# RPI_SSD1963.net
KiCad netlist of a schematic drawn in EAGLE
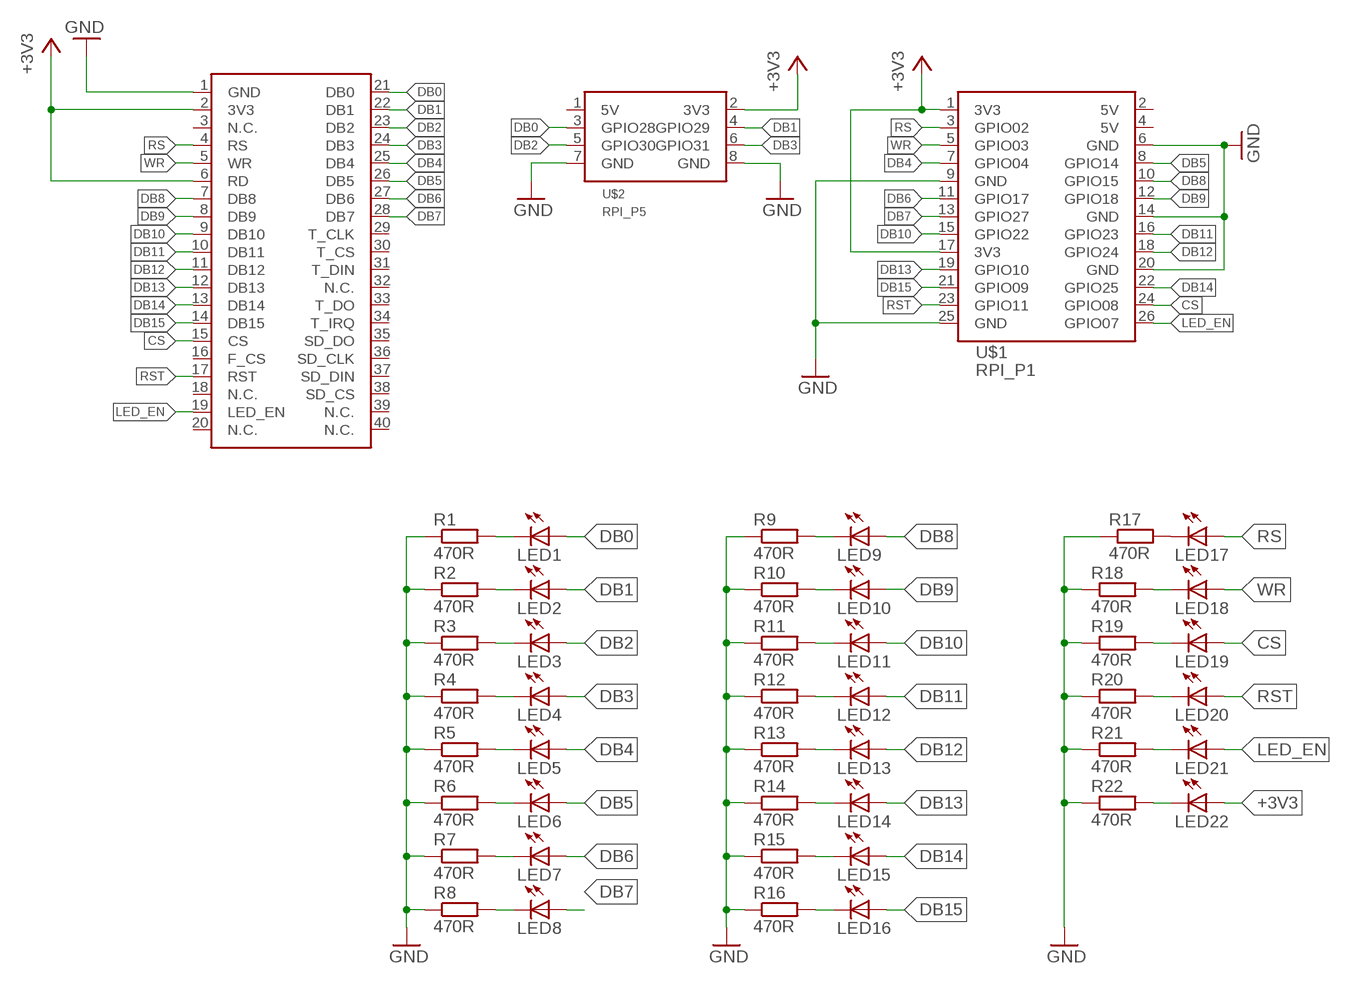
[diagram p0: schematic, sheet 1]

(export (version "E")
  (design (tool "Eeschema 10.0.6"))
  (components
    (comp (ref "LED1")
      (value "LEDCHIP-LED0603")
      (footprint "eagle-import:CHIP-LED0603")
      (libsource (lib "eagle-import") (part "LEDCHIP-LED0603"))
    )
    (comp (ref "LED2")
      (value "LEDCHIP-LED0603")
      (footprint "eagle-import:CHIP-LED0603")
      (libsource (lib "eagle-import") (part "LEDCHIP-LED0603"))
    )
    (comp (ref "LED3")
      (value "LEDCHIP-LED0603")
      (footprint "eagle-import:CHIP-LED0603")
      (libsource (lib "eagle-import") (part "LEDCHIP-LED0603"))
    )
    (comp (ref "LED4")
      (value "LEDCHIP-LED0603")
      (footprint "eagle-import:CHIP-LED0603")
      (libsource (lib "eagle-import") (part "LEDCHIP-LED0603"))
    )
    (comp (ref "LED5")
      (value "LEDCHIP-LED0603")
      (footprint "eagle-import:CHIP-LED0603")
      (libsource (lib "eagle-import") (part "LEDCHIP-LED0603"))
    )
    (comp (ref "LED6")
      (value "LEDCHIP-LED0603")
      (footprint "eagle-import:CHIP-LED0603")
      (libsource (lib "eagle-import") (part "LEDCHIP-LED0603"))
    )
    (comp (ref "LED7")
      (value "LEDCHIP-LED0603")
      (footprint "eagle-import:CHIP-LED0603")
      (libsource (lib "eagle-import") (part "LEDCHIP-LED0603"))
    )
    (comp (ref "LED8")
      (value "LEDCHIP-LED0603")
      (footprint "eagle-import:CHIP-LED0603")
      (libsource (lib "eagle-import") (part "LEDCHIP-LED0603"))
    )
    (comp (ref "LED9")
      (value "LEDCHIP-LED0603")
      (footprint "eagle-import:CHIP-LED0603")
      (libsource (lib "eagle-import") (part "LEDCHIP-LED0603"))
    )
    (comp (ref "LED10")
      (value "LEDCHIP-LED0603")
      (footprint "eagle-import:CHIP-LED0603")
      (libsource (lib "eagle-import") (part "LEDCHIP-LED0603"))
    )
    (comp (ref "LED11")
      (value "LEDCHIP-LED0603")
      (footprint "eagle-import:CHIP-LED0603")
      (libsource (lib "eagle-import") (part "LEDCHIP-LED0603"))
    )
    (comp (ref "LED12")
      (value "LEDCHIP-LED0603")
      (footprint "eagle-import:CHIP-LED0603")
      (libsource (lib "eagle-import") (part "LEDCHIP-LED0603"))
    )
    (comp (ref "LED13")
      (value "LEDCHIP-LED0603")
      (footprint "eagle-import:CHIP-LED0603")
      (libsource (lib "eagle-import") (part "LEDCHIP-LED0603"))
    )
    (comp (ref "LED14")
      (value "LEDCHIP-LED0603")
      (footprint "eagle-import:CHIP-LED0603")
      (libsource (lib "eagle-import") (part "LEDCHIP-LED0603"))
    )
    (comp (ref "LED15")
      (value "LEDCHIP-LED0603")
      (footprint "eagle-import:CHIP-LED0603")
      (libsource (lib "eagle-import") (part "LEDCHIP-LED0603"))
    )
    (comp (ref "LED16")
      (value "LEDCHIP-LED0603")
      (footprint "eagle-import:CHIP-LED0603")
      (libsource (lib "eagle-import") (part "LEDCHIP-LED0603"))
    )
    (comp (ref "LED17")
      (value "LEDCHIP-LED0603")
      (footprint "eagle-import:CHIP-LED0603")
      (libsource (lib "eagle-import") (part "LEDCHIP-LED0603"))
    )
    (comp (ref "LED18")
      (value "LEDCHIP-LED0603")
      (footprint "eagle-import:CHIP-LED0603")
      (libsource (lib "eagle-import") (part "LEDCHIP-LED0603"))
    )
    (comp (ref "LED19")
      (value "LEDCHIP-LED0603")
      (footprint "eagle-import:CHIP-LED0603")
      (libsource (lib "eagle-import") (part "LEDCHIP-LED0603"))
    )
    (comp (ref "LED20")
      (value "LEDCHIP-LED0603")
      (footprint "eagle-import:CHIP-LED0603")
      (libsource (lib "eagle-import") (part "LEDCHIP-LED0603"))
    )
    (comp (ref "LED21")
      (value "LEDCHIP-LED0603")
      (footprint "eagle-import:CHIP-LED0603")
      (libsource (lib "eagle-import") (part "LEDCHIP-LED0603"))
    )
    (comp (ref "LED22")
      (value "LEDCHIP-LED0603")
      (footprint "eagle-import:CHIP-LED0603")
      (libsource (lib "eagle-import") (part "LEDCHIP-LED0603"))
    )
    (comp (ref "R1")
      (value "470R")
      (footprint "eagle-import:R0402")
      (libsource (lib "eagle-import") (part "R-EU_R0402"))
    )
    (comp (ref "R2")
      (value "470R")
      (footprint "eagle-import:R0402")
      (libsource (lib "eagle-import") (part "R-EU_R0402"))
    )
    (comp (ref "R3")
      (value "470R")
      (footprint "eagle-import:R0402")
      (libsource (lib "eagle-import") (part "R-EU_R0402"))
    )
    (comp (ref "R4")
      (value "470R")
      (footprint "eagle-import:R0402")
      (libsource (lib "eagle-import") (part "R-EU_R0402"))
    )
    (comp (ref "R5")
      (value "470R")
      (footprint "eagle-import:R0402")
      (libsource (lib "eagle-import") (part "R-EU_R0402"))
    )
    (comp (ref "R6")
      (value "470R")
      (footprint "eagle-import:R0402")
      (libsource (lib "eagle-import") (part "R-EU_R0402"))
    )
    (comp (ref "R7")
      (value "470R")
      (footprint "eagle-import:R0402")
      (libsource (lib "eagle-import") (part "R-EU_R0402"))
    )
    (comp (ref "R8")
      (value "470R")
      (footprint "eagle-import:R0402")
      (libsource (lib "eagle-import") (part "R-EU_R0402"))
    )
    (comp (ref "R9")
      (value "470R")
      (footprint "eagle-import:R0402")
      (libsource (lib "eagle-import") (part "R-EU_R0402"))
    )
    (comp (ref "R10")
      (value "470R")
      (footprint "eagle-import:R0402")
      (libsource (lib "eagle-import") (part "R-EU_R0402"))
    )
    (comp (ref "R11")
      (value "470R")
      (footprint "eagle-import:R0402")
      (libsource (lib "eagle-import") (part "R-EU_R0402"))
    )
    (comp (ref "R12")
      (value "470R")
      (footprint "eagle-import:R0402")
      (libsource (lib "eagle-import") (part "R-EU_R0402"))
    )
    (comp (ref "R13")
      (value "470R")
      (footprint "eagle-import:R0402")
      (libsource (lib "eagle-import") (part "R-EU_R0402"))
    )
    (comp (ref "R14")
      (value "470R")
      (footprint "eagle-import:R0402")
      (libsource (lib "eagle-import") (part "R-EU_R0402"))
    )
    (comp (ref "R15")
      (value "470R")
      (footprint "eagle-import:R0402")
      (libsource (lib "eagle-import") (part "R-EU_R0402"))
    )
    (comp (ref "R16")
      (value "470R")
      (footprint "eagle-import:R0402")
      (libsource (lib "eagle-import") (part "R-EU_R0402"))
    )
    (comp (ref "R17")
      (value "470R")
      (footprint "eagle-import:R0402")
      (libsource (lib "eagle-import") (part "R-EU_R0402"))
    )
    (comp (ref "R18")
      (value "470R")
      (footprint "eagle-import:R0402")
      (libsource (lib "eagle-import") (part "R-EU_R0402"))
    )
    (comp (ref "R19")
      (value "470R")
      (footprint "eagle-import:R0402")
      (libsource (lib "eagle-import") (part "R-EU_R0402"))
    )
    (comp (ref "R20")
      (value "470R")
      (footprint "eagle-import:R0402")
      (libsource (lib "eagle-import") (part "R-EU_R0402"))
    )
    (comp (ref "R21")
      (value "470R")
      (footprint "eagle-import:R0402")
      (libsource (lib "eagle-import") (part "R-EU_R0402"))
    )
    (comp (ref "R22")
      (value "470R")
      (footprint "eagle-import:R0402")
      (libsource (lib "eagle-import") (part "R-EU_R0402"))
    )
    (comp (ref "U$1")
      (value "RPI_P1")
      (footprint "eagle-import:RPI_P1")
      (libsource (lib "eagle-import") (part "RPI_P1"))
    )
    (comp (ref "U$2")
      (value "RPI_P5")
      (footprint "eagle-import:RPI_P5")
      (libsource (lib "eagle-import") (part "RPI_P5"))
    )
    (comp (ref "U$3")
      (value "SSD1963")
      (footprint "eagle-import:SSD1963")
      (libsource (lib "eagle-import") (part "SSD1963"))
    )
  )
  (nets
    (net (code "1") (name "+3V3") (class "Default")
      (node (ref "LED22") (pin "A") (pinfunction "A_A") (pintype "passive"))
      (node (ref "U$1") (pin "1") (pinfunction "3V3_1") (pintype "bidirectional"))
      (node (ref "U$1") (pin "17") (pinfunction "3V3_17") (pintype "bidirectional"))
      (node (ref "U$2") (pin "2") (pinfunction "3V3_2") (pintype "bidirectional"))
      (node (ref "U$3") (pin "2") (pinfunction "3V3_2") (pintype "passive"))
      (node (ref "U$3") (pin "6") (pinfunction "RD_6") (pintype "bidirectional"))
    )
    (net (code "2") (name "CS") (class "Default")
      (node (ref "LED19") (pin "A") (pinfunction "A_A") (pintype "passive"))
      (node (ref "U$1") (pin "24") (pinfunction "GPIO08_24") (pintype "bidirectional"))
      (node (ref "U$3") (pin "15") (pinfunction "CS_15") (pintype "bidirectional"))
    )
    (net (code "3") (name "DB0") (class "Default")
      (node (ref "LED1") (pin "A") (pinfunction "A_A") (pintype "passive"))
      (node (ref "U$2") (pin "3") (pinfunction "GPIO28_3") (pintype "bidirectional"))
      (node (ref "U$3") (pin "21") (pinfunction "DB0_21") (pintype "bidirectional"))
    )
    (net (code "4") (name "DB1") (class "Default")
      (node (ref "LED2") (pin "A") (pinfunction "A_A") (pintype "passive"))
      (node (ref "U$2") (pin "4") (pinfunction "GPIO29_4") (pintype "bidirectional"))
      (node (ref "U$3") (pin "22") (pinfunction "DB1_22") (pintype "bidirectional"))
    )
    (net (code "5") (name "DB2") (class "Default")
      (node (ref "LED3") (pin "A") (pinfunction "A_A") (pintype "passive"))
      (node (ref "U$2") (pin "5") (pinfunction "GPIO30_5") (pintype "bidirectional"))
      (node (ref "U$3") (pin "23") (pinfunction "DB2_23") (pintype "bidirectional"))
    )
    (net (code "6") (name "DB3") (class "Default")
      (node (ref "LED4") (pin "A") (pinfunction "A_A") (pintype "passive"))
      (node (ref "U$2") (pin "6") (pinfunction "GPIO31_6") (pintype "bidirectional"))
      (node (ref "U$3") (pin "24") (pinfunction "DB3_24") (pintype "bidirectional"))
    )
    (net (code "7") (name "DB4") (class "Default")
      (node (ref "LED5") (pin "A") (pinfunction "A_A") (pintype "passive"))
      (node (ref "U$1") (pin "7") (pinfunction "GPIO04_7") (pintype "bidirectional"))
      (node (ref "U$3") (pin "25") (pinfunction "DB4_25") (pintype "bidirectional"))
    )
    (net (code "8") (name "DB5") (class "Default")
      (node (ref "LED6") (pin "A") (pinfunction "A_A") (pintype "passive"))
      (node (ref "U$1") (pin "8") (pinfunction "GPIO14_8") (pintype "bidirectional"))
      (node (ref "U$3") (pin "26") (pinfunction "DB5_26") (pintype "bidirectional"))
    )
    (net (code "9") (name "DB6") (class "Default")
      (node (ref "LED7") (pin "A") (pinfunction "A_A") (pintype "passive"))
      (node (ref "U$1") (pin "11") (pinfunction "GPIO17_11") (pintype "bidirectional"))
      (node (ref "U$3") (pin "27") (pinfunction "DB6_27") (pintype "bidirectional"))
    )
    (net (code "10") (name "DB7") (class "Default")
      (node (ref "LED8") (pin "A") (pinfunction "A_A") (pintype "passive"))
      (node (ref "U$1") (pin "13") (pinfunction "GPIO27_13") (pintype "bidirectional"))
      (node (ref "U$3") (pin "28") (pinfunction "DB7_28") (pintype "bidirectional"))
    )
    (net (code "11") (name "DB8") (class "Default")
      (node (ref "LED9") (pin "A") (pinfunction "A_A") (pintype "passive"))
      (node (ref "U$1") (pin "10") (pinfunction "GPIO15_10") (pintype "bidirectional"))
      (node (ref "U$3") (pin "7") (pinfunction "DB8_7") (pintype "bidirectional"))
    )
    (net (code "12") (name "DB9") (class "Default")
      (node (ref "LED10") (pin "A") (pinfunction "A_A") (pintype "passive"))
      (node (ref "U$1") (pin "12") (pinfunction "GPIO18_12") (pintype "bidirectional"))
      (node (ref "U$3") (pin "8") (pinfunction "DB9_8") (pintype "bidirectional"))
    )
    (net (code "13") (name "DB10") (class "Default")
      (node (ref "LED11") (pin "A") (pinfunction "A_A") (pintype "passive"))
      (node (ref "U$1") (pin "15") (pinfunction "GPIO22_15") (pintype "bidirectional"))
      (node (ref "U$3") (pin "9") (pinfunction "DB10_9") (pintype "bidirectional"))
    )
    (net (code "14") (name "DB11") (class "Default")
      (node (ref "LED12") (pin "A") (pinfunction "A_A") (pintype "passive"))
      (node (ref "U$1") (pin "16") (pinfunction "GPIO23_16") (pintype "bidirectional"))
      (node (ref "U$3") (pin "10") (pinfunction "DB11_10") (pintype "bidirectional"))
    )
    (net (code "15") (name "DB12") (class "Default")
      (node (ref "LED13") (pin "A") (pinfunction "A_A") (pintype "passive"))
      (node (ref "U$1") (pin "18") (pinfunction "GPIO24_18") (pintype "bidirectional"))
      (node (ref "U$3") (pin "11") (pinfunction "DB12_11") (pintype "bidirectional"))
    )
    (net (code "16") (name "DB13") (class "Default")
      (node (ref "LED14") (pin "A") (pinfunction "A_A") (pintype "passive"))
      (node (ref "U$1") (pin "19") (pinfunction "GPIO10_19") (pintype "bidirectional"))
      (node (ref "U$3") (pin "12") (pinfunction "DB13_12") (pintype "bidirectional"))
    )
    (net (code "17") (name "DB14") (class "Default")
      (node (ref "LED15") (pin "A") (pinfunction "A_A") (pintype "passive"))
      (node (ref "U$1") (pin "22") (pinfunction "GPIO25_22") (pintype "bidirectional"))
      (node (ref "U$3") (pin "13") (pinfunction "DB14_13") (pintype "bidirectional"))
    )
    (net (code "18") (name "DB15") (class "Default")
      (node (ref "LED16") (pin "A") (pinfunction "A_A") (pintype "passive"))
      (node (ref "U$1") (pin "21") (pinfunction "GPIO09_21") (pintype "bidirectional"))
      (node (ref "U$3") (pin "14") (pinfunction "DB15_14") (pintype "bidirectional"))
    )
    (net (code "19") (name "GND") (class "Default")
      (node (ref "R1") (pin "1") (pinfunction "1_1") (pintype "passive"))
      (node (ref "R10") (pin "1") (pinfunction "1_1") (pintype "passive"))
      (node (ref "R11") (pin "1") (pinfunction "1_1") (pintype "passive"))
      (node (ref "R12") (pin "1") (pinfunction "1_1") (pintype "passive"))
      (node (ref "R13") (pin "1") (pinfunction "1_1") (pintype "passive"))
      (node (ref "R14") (pin "1") (pinfunction "1_1") (pintype "passive"))
      (node (ref "R15") (pin "1") (pinfunction "1_1") (pintype "passive"))
      (node (ref "R16") (pin "1") (pinfunction "1_1") (pintype "passive"))
      (node (ref "R17") (pin "1") (pinfunction "1_1") (pintype "passive"))
      (node (ref "R18") (pin "1") (pinfunction "1_1") (pintype "passive"))
      (node (ref "R19") (pin "1") (pinfunction "1_1") (pintype "passive"))
      (node (ref "R2") (pin "1") (pinfunction "1_1") (pintype "passive"))
      (node (ref "R20") (pin "1") (pinfunction "1_1") (pintype "passive"))
      (node (ref "R21") (pin "1") (pinfunction "1_1") (pintype "passive"))
      (node (ref "R22") (pin "1") (pinfunction "1_1") (pintype "passive"))
      (node (ref "R3") (pin "1") (pinfunction "1_1") (pintype "passive"))
      (node (ref "R4") (pin "1") (pinfunction "1_1") (pintype "passive"))
      (node (ref "R5") (pin "1") (pinfunction "1_1") (pintype "passive"))
      (node (ref "R6") (pin "1") (pinfunction "1_1") (pintype "passive"))
      (node (ref "R7") (pin "1") (pinfunction "1_1") (pintype "passive"))
      (node (ref "R8") (pin "1") (pinfunction "1_1") (pintype "passive"))
      (node (ref "R9") (pin "1") (pinfunction "1_1") (pintype "passive"))
      (node (ref "U$1") (pin "14") (pinfunction "GND_14") (pintype "bidirectional"))
      (node (ref "U$1") (pin "20") (pinfunction "GND_20") (pintype "bidirectional"))
      (node (ref "U$1") (pin "25") (pinfunction "GND_25") (pintype "bidirectional"))
      (node (ref "U$1") (pin "6") (pinfunction "GND_6") (pintype "bidirectional"))
      (node (ref "U$1") (pin "9") (pinfunction "GND_9") (pintype "bidirectional"))
      (node (ref "U$2") (pin "7") (pinfunction "GND_7") (pintype "bidirectional"))
      (node (ref "U$2") (pin "8") (pinfunction "GND_8") (pintype "bidirectional"))
      (node (ref "U$3") (pin "1") (pinfunction "GND_1") (pintype "passive"))
    )
    (net (code "20") (name "LED_EN") (class "Default")
      (node (ref "LED21") (pin "A") (pinfunction "A_A") (pintype "passive"))
      (node (ref "U$1") (pin "26") (pinfunction "GPIO07_26") (pintype "bidirectional"))
      (node (ref "U$3") (pin "19") (pinfunction "LED_EN_19") (pintype "bidirectional"))
    )
    (net (code "21") (name "Net-(LED1-PadC)") (class "Default")
      (node (ref "LED1") (pin "C") (pinfunction "C_C") (pintype "passive"))
      (node (ref "R1") (pin "2") (pinfunction "2_2") (pintype "passive"))
    )
    (net (code "22") (name "Net-(LED2-PadC)") (class "Default")
      (node (ref "LED2") (pin "C") (pinfunction "C_C") (pintype "passive"))
      (node (ref "R2") (pin "2") (pinfunction "2_2") (pintype "passive"))
    )
    (net (code "23") (name "Net-(LED3-PadC)") (class "Default")
      (node (ref "LED3") (pin "C") (pinfunction "C_C") (pintype "passive"))
      (node (ref "R3") (pin "2") (pinfunction "2_2") (pintype "passive"))
    )
    (net (code "24") (name "Net-(LED4-PadC)") (class "Default")
      (node (ref "LED4") (pin "C") (pinfunction "C_C") (pintype "passive"))
      (node (ref "R4") (pin "2") (pinfunction "2_2") (pintype "passive"))
    )
    (net (code "25") (name "Net-(LED5-PadC)") (class "Default")
      (node (ref "LED5") (pin "C") (pinfunction "C_C") (pintype "passive"))
      (node (ref "R5") (pin "2") (pinfunction "2_2") (pintype "passive"))
    )
    (net (code "26") (name "Net-(LED6-PadC)") (class "Default")
      (node (ref "LED6") (pin "C") (pinfunction "C_C") (pintype "passive"))
      (node (ref "R6") (pin "2") (pinfunction "2_2") (pintype "passive"))
    )
    (net (code "27") (name "Net-(LED7-PadC)") (class "Default")
      (node (ref "LED7") (pin "C") (pinfunction "C_C") (pintype "passive"))
      (node (ref "R7") (pin "2") (pinfunction "2_2") (pintype "passive"))
    )
    (net (code "28") (name "Net-(LED8-PadC)") (class "Default")
      (node (ref "LED8") (pin "C") (pinfunction "C_C") (pintype "passive"))
      (node (ref "R8") (pin "2") (pinfunction "2_2") (pintype "passive"))
    )
    (net (code "29") (name "Net-(LED9-PadC)") (class "Default")
      (node (ref "LED9") (pin "C") (pinfunction "C_C") (pintype "passive"))
      (node (ref "R9") (pin "2") (pinfunction "2_2") (pintype "passive"))
    )
    (net (code "30") (name "Net-(LED10-PadC)") (class "Default")
      (node (ref "LED10") (pin "C") (pinfunction "C_C") (pintype "passive"))
      (node (ref "R10") (pin "2") (pinfunction "2_2") (pintype "passive"))
    )
    (net (code "31") (name "Net-(LED11-PadC)") (class "Default")
      (node (ref "LED11") (pin "C") (pinfunction "C_C") (pintype "passive"))
      (node (ref "R11") (pin "2") (pinfunction "2_2") (pintype "passive"))
    )
    (net (code "32") (name "Net-(LED12-PadC)") (class "Default")
      (node (ref "LED12") (pin "C") (pinfunction "C_C") (pintype "passive"))
      (node (ref "R12") (pin "2") (pinfunction "2_2") (pintype "passive"))
    )
    (net (code "33") (name "Net-(LED13-PadC)") (class "Default")
      (node (ref "LED13") (pin "C") (pinfunction "C_C") (pintype "passive"))
      (node (ref "R13") (pin "2") (pinfunction "2_2") (pintype "passive"))
    )
    (net (code "34") (name "Net-(LED14-PadC)") (class "Default")
      (node (ref "LED14") (pin "C") (pinfunction "C_C") (pintype "passive"))
      (node (ref "R14") (pin "2") (pinfunction "2_2") (pintype "passive"))
    )
    (net (code "35") (name "Net-(LED15-PadC)") (class "Default")
      (node (ref "LED15") (pin "C") (pinfunction "C_C") (pintype "passive"))
      (node (ref "R15") (pin "2") (pinfunction "2_2") (pintype "passive"))
    )
    (net (code "36") (name "Net-(LED16-PadC)") (class "Default")
      (node (ref "LED16") (pin "C") (pinfunction "C_C") (pintype "passive"))
      (node (ref "R16") (pin "2") (pinfunction "2_2") (pintype "passive"))
    )
    (net (code "37") (name "Net-(LED17-PadC)") (class "Default")
      (node (ref "LED17") (pin "C") (pinfunction "C_C") (pintype "passive"))
      (node (ref "R17") (pin "2") (pinfunction "2_2") (pintype "passive"))
    )
    (net (code "38") (name "Net-(LED18-PadC)") (class "Default")
      (node (ref "LED18") (pin "C") (pinfunction "C_C") (pintype "passive"))
      (node (ref "R18") (pin "2") (pinfunction "2_2") (pintype "passive"))
    )
    (net (code "39") (name "Net-(LED19-PadC)") (class "Default")
      (node (ref "LED19") (pin "C") (pinfunction "C_C") (pintype "passive"))
      (node (ref "R19") (pin "2") (pinfunction "2_2") (pintype "passive"))
    )
    (net (code "40") (name "Net-(LED20-PadC)") (class "Default")
      (node (ref "LED20") (pin "C") (pinfunction "C_C") (pintype "passive"))
      (node (ref "R20") (pin "2") (pinfunction "2_2") (pintype "passive"))
    )
    (net (code "41") (name "Net-(LED21-PadC)") (class "Default")
      (node (ref "LED21") (pin "C") (pinfunction "C_C") (pintype "passive"))
      (node (ref "R21") (pin "2") (pinfunction "2_2") (pintype "passive"))
    )
    (net (code "42") (name "Net-(LED22-PadC)") (class "Default")
      (node (ref "LED22") (pin "C") (pinfunction "C_C") (pintype "passive"))
      (node (ref "R22") (pin "2") (pinfunction "2_2") (pintype "passive"))
    )
    (net (code "43") (name "RS") (class "Default")
      (node (ref "LED17") (pin "A") (pinfunction "A_A") (pintype "passive"))
      (node (ref "U$1") (pin "3") (pinfunction "GPIO02_3") (pintype "bidirectional"))
      (node (ref "U$3") (pin "4") (pinfunction "RS_4") (pintype "bidirectional"))
    )
    (net (code "44") (name "RST") (class "Default")
      (node (ref "LED20") (pin "A") (pinfunction "A_A") (pintype "passive"))
      (node (ref "U$1") (pin "23") (pinfunction "GPIO11_23") (pintype "bidirectional"))
      (node (ref "U$3") (pin "17") (pinfunction "RST_17") (pintype "bidirectional"))
    )
    (net (code "45") (name "WR") (class "Default")
      (node (ref "LED18") (pin "A") (pinfunction "A_A") (pintype "passive"))
      (node (ref "U$1") (pin "5") (pinfunction "GPIO03_5") (pintype "bidirectional"))
      (node (ref "U$3") (pin "5") (pinfunction "WR_5") (pintype "bidirectional"))
    )
    (net (code "46") (name "unconnected-(U$1-5V-Pad2)") (class "Default")
      (node (ref "U$1") (pin "2") (pinfunction "5V_2") (pintype "bidirectional"))
    )
    (net (code "47") (name "unconnected-(U$1-5V-Pad4)") (class "Default")
      (node (ref "U$1") (pin "4") (pinfunction "5V_4") (pintype "bidirectional"))
    )
    (net (code "48") (name "unconnected-(U$2-5V-Pad1)") (class "Default")
      (node (ref "U$2") (pin "1") (pinfunction "5V_1") (pintype "bidirectional"))
    )
    (net (code "49") (name "unconnected-(U$3-F_CS-Pad16)") (class "Default")
      (node (ref "U$3") (pin "16") (pinfunction "F_CS_16") (pintype "bidirectional"))
    )
    (net (code "50") (name "unconnected-(U$3-N.C.-Pad3)") (class "Default")
      (node (ref "U$3") (pin "3") (pinfunction "N.C._3") (pintype "no_connect"))
    )
    (net (code "51") (name "unconnected-(U$3-N.C.-Pad18)") (class "Default")
      (node (ref "U$3") (pin "18") (pinfunction "N.C._18") (pintype "no_connect"))
    )
    (net (code "52") (name "unconnected-(U$3-N.C.-Pad20)") (class "Default")
      (node (ref "U$3") (pin "20") (pinfunction "N.C._20") (pintype "no_connect"))
    )
    (net (code "53") (name "unconnected-(U$3-N.C.-Pad32)") (class "Default")
      (node (ref "U$3") (pin "32") (pinfunction "N.C._32") (pintype "no_connect"))
    )
    (net (code "54") (name "unconnected-(U$3-N.C.-Pad39)") (class "Default")
      (node (ref "U$3") (pin "39") (pinfunction "N.C._39") (pintype "no_connect"))
    )
    (net (code "55") (name "unconnected-(U$3-N.C.-Pad40)") (class "Default")
      (node (ref "U$3") (pin "40") (pinfunction "N.C._40") (pintype "no_connect"))
    )
    (net (code "56") (name "unconnected-(U$3-SD_CLK-Pad36)") (class "Default")
      (node (ref "U$3") (pin "36") (pinfunction "SD_CLK_36") (pintype "bidirectional"))
    )
    (net (code "57") (name "unconnected-(U$3-SD_CS-Pad38)") (class "Default")
      (node (ref "U$3") (pin "38") (pinfunction "SD_CS_38") (pintype "bidirectional"))
    )
    (net (code "58") (name "unconnected-(U$3-SD_DIN-Pad37)") (class "Default")
      (node (ref "U$3") (pin "37") (pinfunction "SD_DIN_37") (pintype "bidirectional"))
    )
    (net (code "59") (name "unconnected-(U$3-SD_DO-Pad35)") (class "Default")
      (node (ref "U$3") (pin "35") (pinfunction "SD_DO_35") (pintype "bidirectional"))
    )
    (net (code "60") (name "unconnected-(U$3-T_CLK-Pad29)") (class "Default")
      (node (ref "U$3") (pin "29") (pinfunction "T_CLK_29") (pintype "bidirectional"))
    )
    (net (code "61") (name "unconnected-(U$3-T_CS-Pad30)") (class "Default")
      (node (ref "U$3") (pin "30") (pinfunction "T_CS_30") (pintype "bidirectional"))
    )
    (net (code "62") (name "unconnected-(U$3-T_DIN-Pad31)") (class "Default")
      (node (ref "U$3") (pin "31") (pinfunction "T_DIN_31") (pintype "bidirectional"))
    )
    (net (code "63") (name "unconnected-(U$3-T_DO-Pad33)") (class "Default")
      (node (ref "U$3") (pin "33") (pinfunction "T_DO_33") (pintype "bidirectional"))
    )
    (net (code "64") (name "unconnected-(U$3-T_IRQ-Pad34)") (class "Default")
      (node (ref "U$3") (pin "34") (pinfunction "T_IRQ_34") (pintype "bidirectional"))
    )
  )
)
